# dc_q84_v1.net
KiCad netlist of a schematic drawn in EAGLE
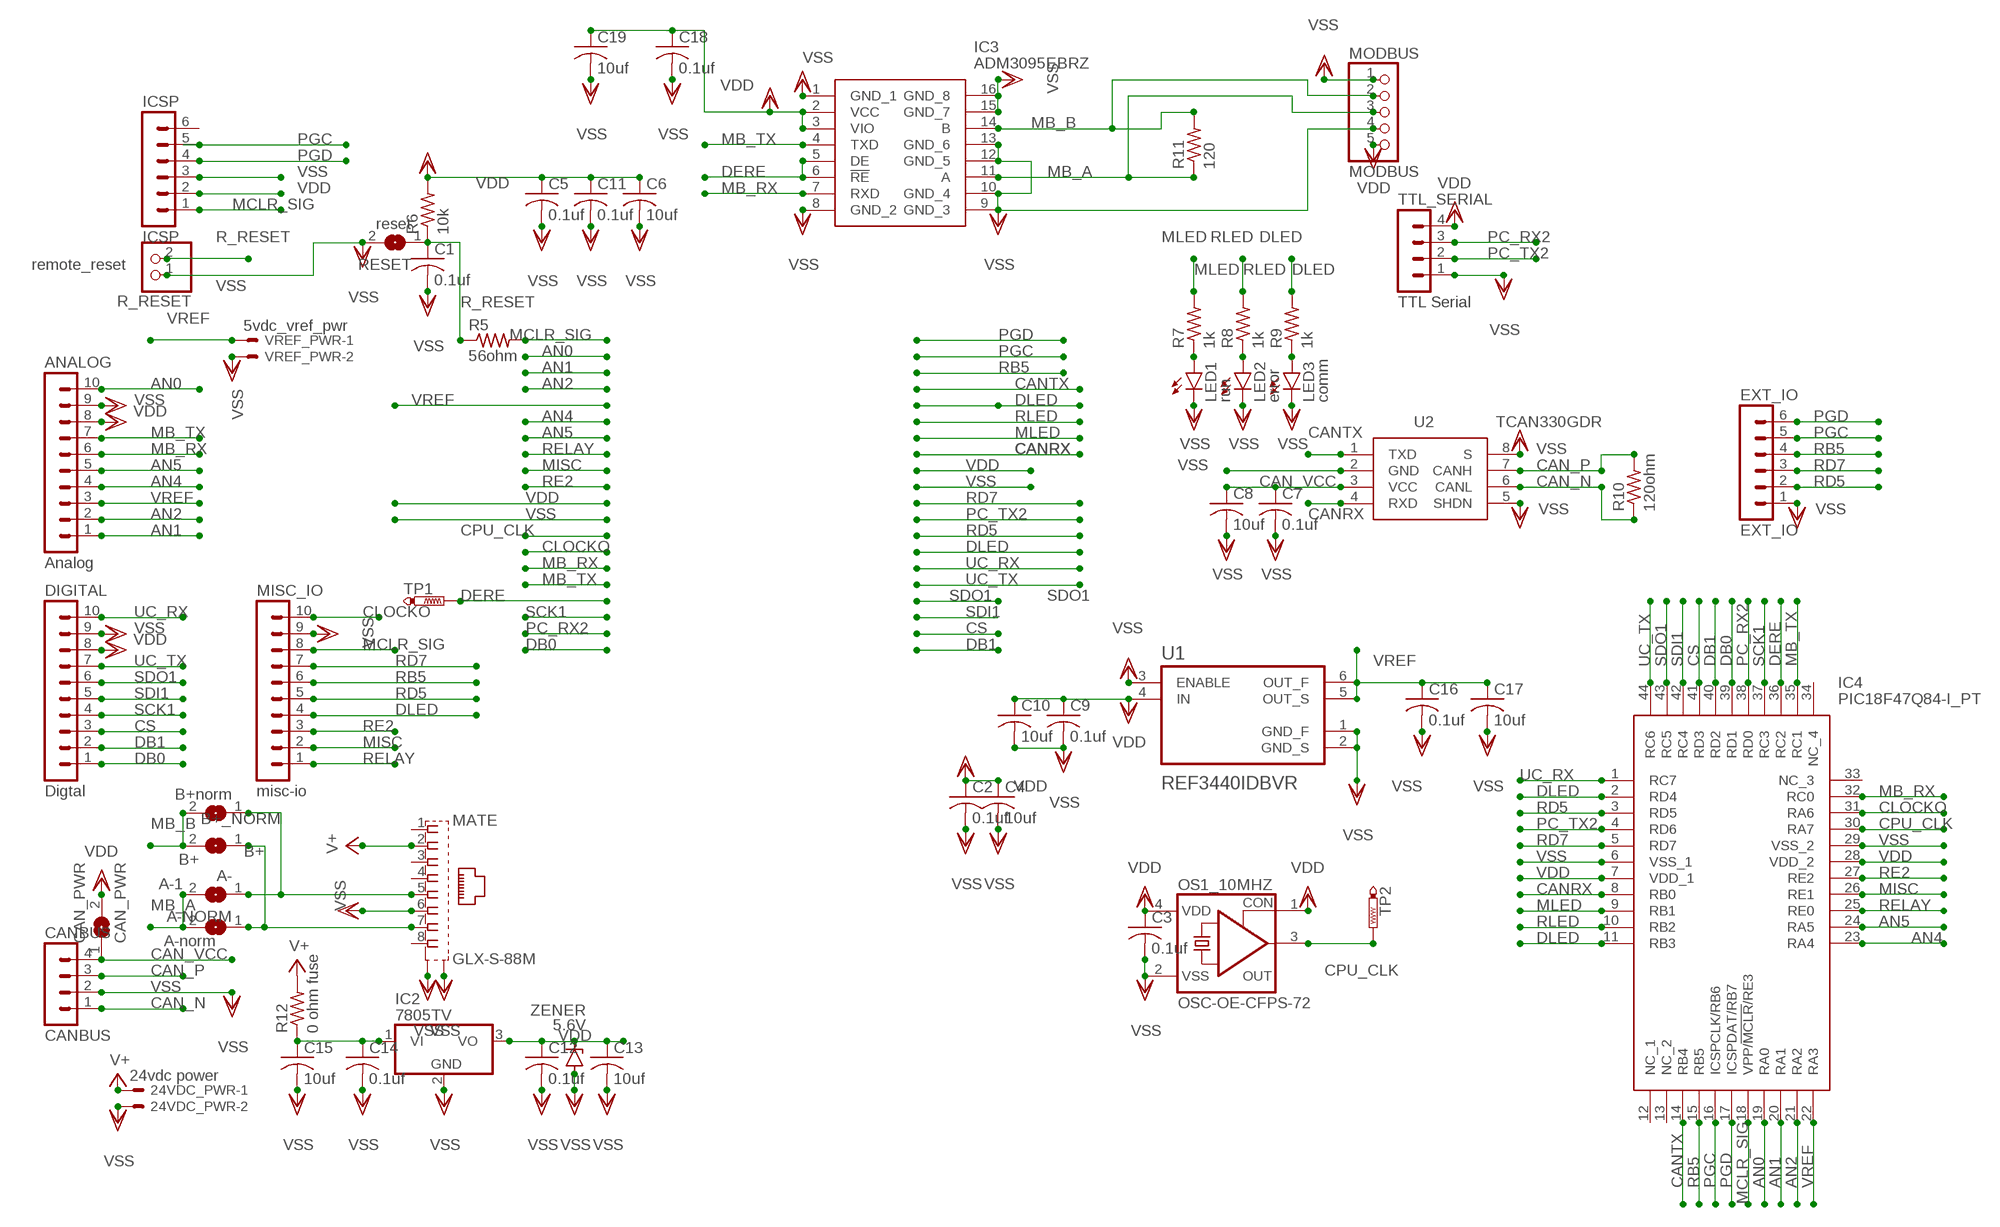
[diagram p0: schematic, sheet 1]

(export (version "E")
  (design (tool "Eeschema 10.0.6"))
  (components
    (comp (ref "24VDC_PWR")
      (value "24vdc power")
      (footprint "eagle-import:22-23-2021")
      (fields (field (name "MF") "MOLEX") (field (name "MPN") "22-23-2021"))
      (libsource (lib "eagle-import") (part "22-23-2021"))
    )
    (comp (ref "A-1") (value "A-") (footprint "eagle-import:SJ") (libsource (lib "eagle-import") (part "SJ")))
    (comp (ref "A-NORM")
      (value "A-norm")
      (footprint "eagle-import:SJ")
      (libsource (lib "eagle-import") (part "SJ"))
    )
    (comp (ref "ANALOG")
      (value "Analog")
      (footprint "eagle-import:MA10-1")
      (libsource (lib "eagle-import") (part "MA10-1"))
    )
    (comp (ref "B+") (value "B+") (footprint "eagle-import:SJ") (libsource (lib "eagle-import") (part "SJ")))
    (comp (ref "B+_NORM")
      (value "B+norm")
      (footprint "eagle-import:SJ")
      (libsource (lib "eagle-import") (part "SJ"))
    )
    (comp (ref "C1")
      (value "0.1uf")
      (footprint "eagle-import:C0805")
      (libsource (lib "eagle-import") (part "C-USC0805"))
    )
    (comp (ref "C2")
      (value "0.1uf")
      (footprint "eagle-import:C0805")
      (libsource (lib "eagle-import") (part "C-USC0805"))
    )
    (comp (ref "C3")
      (value "0.1uf")
      (footprint "eagle-import:C0805")
      (libsource (lib "eagle-import") (part "C-USC0805"))
    )
    (comp (ref "C4")
      (value "10uf")
      (footprint "eagle-import:C0805")
      (libsource (lib "eagle-import") (part "C-USC0805"))
    )
    (comp (ref "C5")
      (value "0.1uf")
      (footprint "eagle-import:C0805")
      (libsource (lib "eagle-import") (part "C-USC0805"))
    )
    (comp (ref "C6")
      (value "10uf")
      (footprint "eagle-import:C0805")
      (libsource (lib "eagle-import") (part "C-USC0805"))
    )
    (comp (ref "C7")
      (value "0.1uf")
      (footprint "eagle-import:C0805")
      (libsource (lib "eagle-import") (part "C-USC0805"))
    )
    (comp (ref "C8")
      (value "10uf")
      (footprint "eagle-import:C0805")
      (libsource (lib "eagle-import") (part "C-USC0805"))
    )
    (comp (ref "C9")
      (value "0.1uf")
      (footprint "eagle-import:C0805")
      (libsource (lib "eagle-import") (part "C-USC0805"))
    )
    (comp (ref "C10")
      (value "10uf")
      (footprint "eagle-import:C0805")
      (libsource (lib "eagle-import") (part "C-USC0805"))
    )
    (comp (ref "C11")
      (value "0.1uf")
      (footprint "eagle-import:C0805")
      (libsource (lib "eagle-import") (part "C-USC0805"))
    )
    (comp (ref "C12")
      (value "0.1uf")
      (footprint "eagle-import:C0805")
      (libsource (lib "eagle-import") (part "C-USC0805"))
    )
    (comp (ref "C13")
      (value "10uf")
      (footprint "eagle-import:C0805")
      (libsource (lib "eagle-import") (part "C-USC0805"))
    )
    (comp (ref "C14")
      (value "0.1uf")
      (footprint "eagle-import:C0805")
      (libsource (lib "eagle-import") (part "C-USC0805"))
    )
    (comp (ref "C15")
      (value "10uf")
      (footprint "eagle-import:C0805")
      (libsource (lib "eagle-import") (part "C-USC0805"))
    )
    (comp (ref "C16")
      (value "0.1uf")
      (footprint "eagle-import:C0805")
      (libsource (lib "eagle-import") (part "C-USC0805"))
    )
    (comp (ref "C17")
      (value "10uf")
      (footprint "eagle-import:C0805")
      (libsource (lib "eagle-import") (part "C-USC0805"))
    )
    (comp (ref "C18")
      (value "0.1uf")
      (footprint "eagle-import:C0805")
      (libsource (lib "eagle-import") (part "C-USC0805"))
    )
    (comp (ref "C19")
      (value "10uf")
      (footprint "eagle-import:C0805")
      (libsource (lib "eagle-import") (part "C-USC0805"))
    )
    (comp (ref "CANBUS")
      (value "CANBUS")
      (footprint "eagle-import:MA04-1")
      (libsource (lib "eagle-import") (part "MA04-1"))
    )
    (comp (ref "CAN_PWR")
      (value "CAN_PWR")
      (footprint "eagle-import:SJ")
      (libsource (lib "eagle-import") (part "SJ"))
    )
    (comp (ref "DIGITAL")
      (value "Digtal")
      (footprint "eagle-import:MA10-1")
      (libsource (lib "eagle-import") (part "MA10-1"))
    )
    (comp (ref "EXT_IO")
      (value "EXT_IO")
      (footprint "eagle-import:MA06-1")
      (libsource (lib "eagle-import") (part "MA06-1"))
    )
    (comp (ref "IC2")
      (value "7805TV")
      (footprint "eagle-import:TO220V")
      (libsource (lib "eagle-import") (part "78TV05"))
    )
    (comp (ref "IC3")
      (value "ADM3095EBRZ")
      (footprint "eagle-import:SOIC127P600X175-16N")
      (fields (field (name "MOUSER_PART_NUMBER") "584-ADM3095EBRZ"))
      (libsource (lib "eagle-import") (part "ADM3095EBRZ"))
    )
    (comp (ref "IC4")
      (value "PIC18F47Q84-I_PT")
      (footprint "eagle-import:QFP80P1200X1200X120-44N")
      (fields
        (field (name "MANUFACTURER_PART_NUMBER") "PIC18F47Q84-I/PT")
        (field (name "MOUSER_PART_NUMBER") "579-PIC18F47Q84-I/PT")
      )
      (libsource (lib "eagle-import") (part "PIC18F47Q84-I_PT"))
    )
    (comp (ref "ICSP")
      (value "ICSP")
      (footprint "eagle-import:MA06-1")
      (libsource (lib "eagle-import") (part "MA06-1"))
    )
    (comp (ref "LED1")
      (value "run")
      (footprint "eagle-import:CHIPLED_0805")
      (libsource (lib "eagle-import") (part "LEDCHIPLED_0805"))
    )
    (comp (ref "LED2")
      (value "error")
      (footprint "eagle-import:CHIPLED_0805")
      (libsource (lib "eagle-import") (part "LEDCHIPLED_0805"))
    )
    (comp (ref "LED3")
      (value "comm")
      (footprint "eagle-import:CHIPLED_0805")
      (libsource (lib "eagle-import") (part "LEDCHIPLED_0805"))
    )
    (comp (ref "MATE")
      (value "GLX-S-88M")
      (footprint "eagle-import:GLX-S-88M")
      (libsource (lib "eagle-import") (part "GLX-S-88M"))
    )
    (comp (ref "MISC_IO")
      (value "misc-io")
      (footprint "eagle-import:MA10-1")
      (libsource (lib "eagle-import") (part "MA10-1"))
    )
    (comp (ref "MODBUS")
      (value "MODBUS")
      (footprint "eagle-import:1X05")
      (libsource (lib "eagle-import") (part "PINHD-1X5"))
    )
    (comp (ref "OS1_10MHZ")
      (value "OSC-OE-CFPS-72")
      (footprint "eagle-import:7.2X5.2-4-PAD")
      (libsource (lib "eagle-import") (part "OSC-OE-CFPS-72"))
    )
    (comp (ref "R5")
      (value "56ohm")
      (footprint "eagle-import:R0805")
      (libsource (lib "eagle-import") (part "R-US_R0805"))
    )
    (comp (ref "R6")
      (value "10k")
      (footprint "eagle-import:R0805")
      (libsource (lib "eagle-import") (part "R-US_R0805"))
    )
    (comp (ref "R7")
      (value "1k")
      (footprint "eagle-import:R0805")
      (libsource (lib "eagle-import") (part "R-US_R0805"))
    )
    (comp (ref "R8")
      (value "1k")
      (footprint "eagle-import:R0805")
      (libsource (lib "eagle-import") (part "R-US_R0805"))
    )
    (comp (ref "R9")
      (value "1k")
      (footprint "eagle-import:R0805")
      (libsource (lib "eagle-import") (part "R-US_R0805"))
    )
    (comp (ref "R10")
      (value "120ohm")
      (footprint "eagle-import:R0805")
      (libsource (lib "eagle-import") (part "R-US_R0805"))
    )
    (comp (ref "R11")
      (value "120")
      (footprint "eagle-import:R0805")
      (libsource (lib "eagle-import") (part "R-US_R0805"))
    )
    (comp (ref "R12")
      (value "0 ohm fuse")
      (footprint "eagle-import:R1206")
      (libsource (lib "eagle-import") (part "R-US_R1206"))
    )
    (comp (ref "RESET")
      (value "reset")
      (footprint "eagle-import:SJ")
      (libsource (lib "eagle-import") (part "SJ"))
    )
    (comp (ref "R_RESET")
      (value "remote_reset")
      (footprint "eagle-import:1X02")
      (libsource (lib "eagle-import") (part "PINHD-1X2"))
    )
    (comp (ref "TP1")
      (value "PTR1PAD1-13")
      (footprint "eagle-import:P1-13")
      (libsource (lib "eagle-import") (part "PTR1PAD1-13"))
    )
    (comp (ref "TP2")
      (value "PTR1PAD1-13")
      (footprint "eagle-import:P1-13")
      (libsource (lib "eagle-import") (part "PTR1PAD1-13"))
    )
    (comp (ref "TTL_SERIAL")
      (value "TTL Serial")
      (footprint "eagle-import:MA04-1")
      (libsource (lib "eagle-import") (part "MA04-1"))
    )
    (comp (ref "U1")
      (value "REF3440IDBVR")
      (footprint "eagle-import:SOT95P280X145-6N")
      (fields (field (name "MF") "Texas Instruments"))
      (libsource (lib "eagle-import") (part "REF3440IDBVR"))
    )
    (comp (ref "U2")
      (value "TCAN330GDR")
      (footprint "eagle-import:SOIC127P600X175-8N")
      (fields (field (name "MOUSER_PART_NUMBER") "595-TCAN330GDR"))
      (libsource (lib "eagle-import") (part "TCAN330GDR"))
    )
    (comp (ref "VREF_PWR")
      (value "5vdc_vref_pwr")
      (footprint "eagle-import:22-23-2021")
      (fields (field (name "MF") "MOLEX") (field (name "MPN") "22-23-2021"))
      (libsource (lib "eagle-import") (part "22-23-2021"))
    )
    (comp (ref "ZENER")
      (value "5.6V")
      (footprint "eagle-import:SMB")
      (libsource (lib "eagle-import") (part "ZENER-DIODESMB"))
    )
  )
  (nets
    (net (code "1") (name "/AN0") (class "Default")
      (node (ref "ANALOG") (pin "10") (pinfunction "10_10") (pintype "passive"))
      (node (ref "IC4") (pin "19") (pinfunction "RA0_19") (pintype "bidirectional"))
    )
    (net (code "2") (name "/AN1") (class "Default")
      (node (ref "ANALOG") (pin "1") (pinfunction "1_1") (pintype "passive"))
      (node (ref "IC4") (pin "20") (pinfunction "RA1_20") (pintype "bidirectional"))
    )
    (net (code "3") (name "/AN2") (class "Default")
      (node (ref "ANALOG") (pin "2") (pinfunction "2_2") (pintype "passive"))
      (node (ref "IC4") (pin "21") (pinfunction "RA2_21") (pintype "bidirectional"))
    )
    (net (code "4") (name "/AN4") (class "Default")
      (node (ref "ANALOG") (pin "4") (pinfunction "4_4") (pintype "passive"))
      (node (ref "IC4") (pin "23") (pinfunction "RA4_23") (pintype "bidirectional"))
    )
    (net (code "5") (name "/AN5") (class "Default")
      (node (ref "ANALOG") (pin "5") (pinfunction "5_5") (pintype "passive"))
      (node (ref "IC4") (pin "24") (pinfunction "RA5_24") (pintype "bidirectional"))
    )
    (net (code "6") (name "/CANRX") (class "Default")
      (node (ref "IC4") (pin "8") (pinfunction "RB0_8") (pintype "bidirectional"))
      (node (ref "U2") (pin "4") (pinfunction "RXD_4") (pintype "output"))
    )
    (net (code "7") (name "/CANTX") (class "Default")
      (node (ref "IC4") (pin "14") (pinfunction "RB4_14") (pintype "bidirectional"))
      (node (ref "U2") (pin "1") (pinfunction "TXD_1") (pintype "input"))
    )
    (net (code "8") (name "/CAN_N") (class "Default")
      (node (ref "CANBUS") (pin "1") (pinfunction "1_1") (pintype "passive"))
      (node (ref "R10") (pin "1") (pinfunction "1_1") (pintype "passive"))
      (node (ref "U2") (pin "6") (pinfunction "CANL_6") (pintype "bidirectional"))
    )
    (net (code "9") (name "/CAN_P") (class "Default")
      (node (ref "CANBUS") (pin "3") (pinfunction "3_3") (pintype "passive"))
      (node (ref "R10") (pin "2") (pinfunction "2_2") (pintype "passive"))
      (node (ref "U2") (pin "7") (pinfunction "CANH_7") (pintype "bidirectional"))
    )
    (net (code "10") (name "/CAN_VCC") (class "Default")
      (node (ref "C7") (pin "1") (pinfunction "1_1") (pintype "passive"))
      (node (ref "C8") (pin "1") (pinfunction "1_1") (pintype "passive"))
      (node (ref "CANBUS") (pin "4") (pinfunction "4_4") (pintype "passive"))
      (node (ref "CAN_PWR") (pin "1") (pinfunction "1_1") (pintype "passive"))
      (node (ref "U2") (pin "3") (pinfunction "VCC_3") (pintype "power_in"))
    )
    (net (code "11") (name "/CLOCKO") (class "Default")
      (node (ref "IC4") (pin "31") (pinfunction "RA6_31") (pintype "bidirectional"))
      (node (ref "MISC_IO") (pin "10") (pinfunction "10_10") (pintype "passive"))
    )
    (net (code "12") (name "/CPU_CLK") (class "Default")
      (node (ref "IC4") (pin "30") (pinfunction "RA7_30") (pintype "bidirectional"))
      (node (ref "OS1_10MHZ") (pin "3") (pinfunction "OUT_3") (pintype "output"))
      (node (ref "TP2") (pin "TP") (pinfunction "TP_TP") (pintype "input"))
    )
    (net (code "13") (name "/CS") (class "Default")
      (node (ref "DIGITAL") (pin "3") (pinfunction "3_3") (pintype "passive"))
      (node (ref "IC4") (pin "41") (pinfunction "RD3_41") (pintype "bidirectional"))
    )
    (net (code "14") (name "/DB0") (class "Default")
      (node (ref "DIGITAL") (pin "1") (pinfunction "1_1") (pintype "passive"))
      (node (ref "IC4") (pin "39") (pinfunction "RD1_39") (pintype "bidirectional"))
    )
    (net (code "15") (name "/DB1") (class "Default")
      (node (ref "DIGITAL") (pin "2") (pinfunction "2_2") (pintype "passive"))
      (node (ref "IC4") (pin "40") (pinfunction "RD2_40") (pintype "bidirectional"))
    )
    (net (code "16") (name "/DERE") (class "Default")
      (node (ref "IC3") (pin "5") (pinfunction "DE_5") (pintype "input"))
      (node (ref "IC3") (pin "6") (pinfunction "~{RE}_6") (pintype "input"))
      (node (ref "IC4") (pin "36") (pinfunction "RC2_36") (pintype "bidirectional"))
      (node (ref "TP1") (pin "TP") (pinfunction "TP_TP") (pintype "input"))
    )
    (net (code "17") (name "/DLED") (class "Default")
      (node (ref "IC4") (pin "11") (pinfunction "RB3_11") (pintype "bidirectional"))
      (node (ref "IC4") (pin "2") (pinfunction "RD4_2") (pintype "bidirectional"))
      (node (ref "MISC_IO") (pin "4") (pinfunction "4_4") (pintype "passive"))
      (node (ref "R9") (pin "2") (pinfunction "2_2") (pintype "passive"))
    )
    (net (code "18") (name "/MB_A") (class "Default")
      (node (ref "A-1") (pin "2") (pinfunction "2_2") (pintype "passive"))
      (node (ref "A-NORM") (pin "2") (pinfunction "2_2") (pintype "passive"))
      (node (ref "IC3") (pin "11") (pinfunction "A_11") (pintype "bidirectional"))
      (node (ref "MODBUS") (pin "3") (pinfunction "3_3") (pintype "passive"))
      (node (ref "R11") (pin "1") (pinfunction "1_1") (pintype "passive"))
    )
    (net (code "19") (name "/MB_B") (class "Default")
      (node (ref "B+") (pin "2") (pinfunction "2_2") (pintype "passive"))
      (node (ref "B+_NORM") (pin "2") (pinfunction "2_2") (pintype "passive"))
      (node (ref "IC3") (pin "14") (pinfunction "B_14") (pintype "bidirectional"))
      (node (ref "MODBUS") (pin "2") (pinfunction "2_2") (pintype "passive"))
      (node (ref "R11") (pin "2") (pinfunction "2_2") (pintype "passive"))
    )
    (net (code "20") (name "/MB_RX") (class "Default")
      (node (ref "ANALOG") (pin "6") (pinfunction "6_6") (pintype "passive"))
      (node (ref "IC3") (pin "7") (pinfunction "RXD_7") (pintype "output"))
      (node (ref "IC4") (pin "32") (pinfunction "RC0_32") (pintype "bidirectional"))
    )
    (net (code "21") (name "/MB_TX") (class "Default")
      (node (ref "ANALOG") (pin "7") (pinfunction "7_7") (pintype "passive"))
      (node (ref "IC3") (pin "4") (pinfunction "TXD_4") (pintype "input"))
      (node (ref "IC4") (pin "35") (pinfunction "RC1_35") (pintype "bidirectional"))
    )
    (net (code "22") (name "/MCLR_SIG") (class "Default")
      (node (ref "IC4") (pin "18") (pinfunction "VPP/~{MCLR}/RE3_18") (pintype "bidirectional"))
      (node (ref "ICSP") (pin "1") (pinfunction "1_1") (pintype "passive"))
      (node (ref "MISC_IO") (pin "8") (pinfunction "8_8") (pintype "passive"))
      (node (ref "R5") (pin "2") (pinfunction "2_2") (pintype "passive"))
    )
    (net (code "23") (name "/MISC") (class "Default")
      (node (ref "IC4") (pin "26") (pinfunction "RE1_26") (pintype "bidirectional"))
      (node (ref "MISC_IO") (pin "2") (pinfunction "2_2") (pintype "passive"))
    )
    (net (code "24") (name "/MLED") (class "Default")
      (node (ref "IC4") (pin "9") (pinfunction "RB1_9") (pintype "bidirectional"))
      (node (ref "R7") (pin "2") (pinfunction "2_2") (pintype "passive"))
    )
    (net (code "25") (name "/PC_RX2") (class "Default")
      (node (ref "IC4") (pin "38") (pinfunction "RD0_38") (pintype "bidirectional"))
      (node (ref "TTL_SERIAL") (pin "3") (pinfunction "3_3") (pintype "passive"))
    )
    (net (code "26") (name "/PC_TX2") (class "Default")
      (node (ref "IC4") (pin "4") (pinfunction "RD6_4") (pintype "bidirectional"))
      (node (ref "TTL_SERIAL") (pin "2") (pinfunction "2_2") (pintype "passive"))
    )
    (net (code "27") (name "/PGC") (class "Default")
      (node (ref "EXT_IO") (pin "5") (pinfunction "5_5") (pintype "passive"))
      (node (ref "IC4") (pin "16") (pinfunction "ICSPCLK/RB6_16") (pintype "bidirectional"))
      (node (ref "ICSP") (pin "5") (pinfunction "5_5") (pintype "passive"))
    )
    (net (code "28") (name "/PGD") (class "Default")
      (node (ref "EXT_IO") (pin "6") (pinfunction "6_6") (pintype "passive"))
      (node (ref "IC4") (pin "17") (pinfunction "ICSPDAT/RB7_17") (pintype "bidirectional"))
      (node (ref "ICSP") (pin "4") (pinfunction "4_4") (pintype "passive"))
    )
    (net (code "29") (name "/RB5") (class "Default")
      (node (ref "EXT_IO") (pin "4") (pinfunction "4_4") (pintype "passive"))
      (node (ref "IC4") (pin "15") (pinfunction "RB5_15") (pintype "bidirectional"))
      (node (ref "MISC_IO") (pin "6") (pinfunction "6_6") (pintype "passive"))
    )
    (net (code "30") (name "/RD5") (class "Default")
      (node (ref "EXT_IO") (pin "2") (pinfunction "2_2") (pintype "passive"))
      (node (ref "IC4") (pin "3") (pinfunction "RD5_3") (pintype "bidirectional"))
      (node (ref "MISC_IO") (pin "5") (pinfunction "5_5") (pintype "passive"))
    )
    (net (code "31") (name "/RD7") (class "Default")
      (node (ref "EXT_IO") (pin "3") (pinfunction "3_3") (pintype "passive"))
      (node (ref "IC4") (pin "5") (pinfunction "RD7_5") (pintype "bidirectional"))
      (node (ref "MISC_IO") (pin "7") (pinfunction "7_7") (pintype "passive"))
    )
    (net (code "32") (name "/RE2") (class "Default")
      (node (ref "IC4") (pin "27") (pinfunction "RE2_27") (pintype "bidirectional"))
      (node (ref "MISC_IO") (pin "3") (pinfunction "3_3") (pintype "passive"))
    )
    (net (code "33") (name "/RELAY") (class "Default")
      (node (ref "IC4") (pin "25") (pinfunction "RE0_25") (pintype "bidirectional"))
      (node (ref "MISC_IO") (pin "1") (pinfunction "1_1") (pintype "passive"))
    )
    (net (code "34") (name "/RLED") (class "Default")
      (node (ref "IC4") (pin "10") (pinfunction "RB2_10") (pintype "bidirectional"))
      (node (ref "R8") (pin "2") (pinfunction "2_2") (pintype "passive"))
    )
    (net (code "35") (name "/R_RESET") (class "Default")
      (node (ref "C1") (pin "1") (pinfunction "1_1") (pintype "passive"))
      (node (ref "R5") (pin "1") (pinfunction "1_1") (pintype "passive"))
      (node (ref "R6") (pin "1") (pinfunction "1_1") (pintype "passive"))
      (node (ref "RESET") (pin "1") (pinfunction "1_1") (pintype "passive"))
      (node (ref "R_RESET") (pin "2") (pinfunction "2_2") (pintype "passive"))
    )
    (net (code "36") (name "/SCK1") (class "Default")
      (node (ref "DIGITAL") (pin "4") (pinfunction "4_4") (pintype "passive"))
      (node (ref "IC4") (pin "37") (pinfunction "RC3_37") (pintype "bidirectional"))
    )
    (net (code "37") (name "/SDI1") (class "Default")
      (node (ref "DIGITAL") (pin "5") (pinfunction "5_5") (pintype "passive"))
      (node (ref "IC4") (pin "42") (pinfunction "RC4_42") (pintype "bidirectional"))
    )
    (net (code "38") (name "/SDO1") (class "Default")
      (node (ref "DIGITAL") (pin "6") (pinfunction "6_6") (pintype "passive"))
      (node (ref "IC4") (pin "43") (pinfunction "RC5_43") (pintype "bidirectional"))
    )
    (net (code "39") (name "/UC_RX") (class "Default")
      (node (ref "DIGITAL") (pin "10") (pinfunction "10_10") (pintype "passive"))
      (node (ref "IC4") (pin "1") (pinfunction "RC7_1") (pintype "bidirectional"))
    )
    (net (code "40") (name "/UC_TX") (class "Default")
      (node (ref "DIGITAL") (pin "7") (pinfunction "7_7") (pintype "passive"))
      (node (ref "IC4") (pin "44") (pinfunction "RC6_44") (pintype "bidirectional"))
    )
    (net (code "41") (name "/VREF") (class "Default")
      (node (ref "ANALOG") (pin "3") (pinfunction "3_3") (pintype "passive"))
      (node (ref "C16") (pin "1") (pinfunction "1_1") (pintype "passive"))
      (node (ref "C17") (pin "1") (pinfunction "1_1") (pintype "passive"))
      (node (ref "IC4") (pin "22") (pinfunction "RA3_22") (pintype "bidirectional"))
      (node (ref "U1") (pin "5") (pinfunction "OUT_S_5") (pintype "output"))
      (node (ref "U1") (pin "6") (pinfunction "OUT_F_6") (pintype "output"))
      (node (ref "VREF_PWR") (pin "1") (pinfunction "S_1") (pintype "passive"))
    )
    (net (code "42") (name "Net-(A-1-Pad1)") (class "Default")
      (node (ref "A-1") (pin "1") (pinfunction "1_1") (pintype "passive"))
      (node (ref "B+_NORM") (pin "1") (pinfunction "1_1") (pintype "passive"))
      (node (ref "MATE") (pin "5") (pinfunction "5_5") (pintype "passive"))
    )
    (net (code "43") (name "Net-(A-NORM-Pad1)") (class "Default")
      (node (ref "A-NORM") (pin "1") (pinfunction "1_1") (pintype "passive"))
      (node (ref "B+") (pin "1") (pinfunction "1_1") (pintype "passive"))
      (node (ref "MATE") (pin "7") (pinfunction "7_7") (pintype "passive"))
    )
    (net (code "44") (name "Net-(IC2-VI)") (class "Default")
      (node (ref "C14") (pin "1") (pinfunction "1_1") (pintype "passive"))
      (node (ref "C15") (pin "1") (pinfunction "1_1") (pintype "passive"))
      (node (ref "IC2") (pin "1") (pinfunction "VI_1") (pintype "input"))
      (node (ref "R12") (pin "1") (pinfunction "1_1") (pintype "passive"))
    )
    (net (code "45") (name "Net-(LED1-PadA)") (class "Default")
      (node (ref "LED1") (pin "A") (pinfunction "A_A") (pintype "passive"))
      (node (ref "R7") (pin "1") (pinfunction "1_1") (pintype "passive"))
    )
    (net (code "46") (name "Net-(LED2-PadA)") (class "Default")
      (node (ref "LED2") (pin "A") (pinfunction "A_A") (pintype "passive"))
      (node (ref "R8") (pin "1") (pinfunction "1_1") (pintype "passive"))
    )
    (net (code "47") (name "Net-(LED3-PadA)") (class "Default")
      (node (ref "LED3") (pin "A") (pinfunction "A_A") (pintype "passive"))
      (node (ref "R9") (pin "1") (pinfunction "1_1") (pintype "passive"))
    )
    (net (code "48") (name "V+") (class "Default")
      (node (ref "24VDC_PWR") (pin "1") (pinfunction "S_1") (pintype "passive"))
      (node (ref "MATE") (pin "2") (pinfunction "2_2") (pintype "passive"))
      (node (ref "R12") (pin "2") (pinfunction "2_2") (pintype "passive"))
    )
    (net (code "49") (name "VDD") (class "Default")
      (node (ref "ANALOG") (pin "8") (pinfunction "8_8") (pintype "passive"))
      (node (ref "C10") (pin "1") (pinfunction "1_1") (pintype "passive"))
      (node (ref "C11") (pin "1") (pinfunction "1_1") (pintype "passive"))
      (node (ref "C12") (pin "1") (pinfunction "1_1") (pintype "passive"))
      (node (ref "C13") (pin "1") (pinfunction "1_1") (pintype "passive"))
      (node (ref "C18") (pin "1") (pinfunction "1_1") (pintype "passive"))
      (node (ref "C19") (pin "1") (pinfunction "1_1") (pintype "passive"))
      (node (ref "C2") (pin "1") (pinfunction "1_1") (pintype "passive"))
      (node (ref "C3") (pin "1") (pinfunction "1_1") (pintype "passive"))
      (node (ref "C4") (pin "1") (pinfunction "1_1") (pintype "passive"))
      (node (ref "C5") (pin "1") (pinfunction "1_1") (pintype "passive"))
      (node (ref "C6") (pin "1") (pinfunction "1_1") (pintype "passive"))
      (node (ref "C9") (pin "1") (pinfunction "1_1") (pintype "passive"))
      (node (ref "CAN_PWR") (pin "2") (pinfunction "2_2") (pintype "passive"))
      (node (ref "DIGITAL") (pin "8") (pinfunction "8_8") (pintype "passive"))
      (node (ref "IC2") (pin "3") (pinfunction "VO_3") (pintype "passive"))
      (node (ref "IC3") (pin "2") (pinfunction "VCC_2") (pintype "power_in"))
      (node (ref "IC3") (pin "3") (pinfunction "VIO_3") (pintype "power_in"))
      (node (ref "IC4") (pin "28") (pinfunction "VDD_2_28") (pintype "bidirectional"))
      (node (ref "IC4") (pin "7") (pinfunction "VDD_1_7") (pintype "bidirectional"))
      (node (ref "ICSP") (pin "2") (pinfunction "2_2") (pintype "passive"))
      (node (ref "MODBUS") (pin "5") (pinfunction "5_5") (pintype "passive"))
      (node (ref "OS1_10MHZ") (pin "1") (pinfunction "CON_1") (pintype "input"))
      (node (ref "OS1_10MHZ") (pin "4") (pinfunction "VDD_4") (pintype "power_in"))
      (node (ref "R6") (pin "2") (pinfunction "2_2") (pintype "passive"))
      (node (ref "TTL_SERIAL") (pin "4") (pinfunction "4_4") (pintype "passive"))
      (node (ref "U1") (pin "4") (pinfunction "IN_4") (pintype "input"))
      (node (ref "ZENER") (pin "C") (pinfunction "C_C") (pintype "passive"))
    )
    (net (code "50") (name "VSS") (class "Default")
      (node (ref "24VDC_PWR") (pin "2") (pinfunction "S_2") (pintype "passive"))
      (node (ref "ANALOG") (pin "9") (pinfunction "9_9") (pintype "passive"))
      (node (ref "C1") (pin "2") (pinfunction "2_2") (pintype "passive"))
      (node (ref "C10") (pin "2") (pinfunction "2_2") (pintype "passive"))
      (node (ref "C11") (pin "2") (pinfunction "2_2") (pintype "passive"))
      (node (ref "C12") (pin "2") (pinfunction "2_2") (pintype "passive"))
      (node (ref "C13") (pin "2") (pinfunction "2_2") (pintype "passive"))
      (node (ref "C14") (pin "2") (pinfunction "2_2") (pintype "passive"))
      (node (ref "C15") (pin "2") (pinfunction "2_2") (pintype "passive"))
      (node (ref "C16") (pin "2") (pinfunction "2_2") (pintype "passive"))
      (node (ref "C17") (pin "2") (pinfunction "2_2") (pintype "passive"))
      (node (ref "C18") (pin "2") (pinfunction "2_2") (pintype "passive"))
      (node (ref "C19") (pin "2") (pinfunction "2_2") (pintype "passive"))
      (node (ref "C2") (pin "2") (pinfunction "2_2") (pintype "passive"))
      (node (ref "C3") (pin "2") (pinfunction "2_2") (pintype "passive"))
      (node (ref "C4") (pin "2") (pinfunction "2_2") (pintype "passive"))
      (node (ref "C5") (pin "2") (pinfunction "2_2") (pintype "passive"))
      (node (ref "C6") (pin "2") (pinfunction "2_2") (pintype "passive"))
      (node (ref "C7") (pin "2") (pinfunction "2_2") (pintype "passive"))
      (node (ref "C8") (pin "2") (pinfunction "2_2") (pintype "passive"))
      (node (ref "C9") (pin "2") (pinfunction "2_2") (pintype "passive"))
      (node (ref "CANBUS") (pin "2") (pinfunction "2_2") (pintype "passive"))
      (node (ref "DIGITAL") (pin "9") (pinfunction "9_9") (pintype "passive"))
      (node (ref "EXT_IO") (pin "1") (pinfunction "1_1") (pintype "passive"))
      (node (ref "IC2") (pin "2") (pinfunction "GND_2") (pintype "passive"))
      (node (ref "IC3") (pin "1") (pinfunction "GND_1_1") (pintype "power_in"))
      (node (ref "IC3") (pin "10") (pinfunction "GND_4_10") (pintype "power_in"))
      (node (ref "IC3") (pin "12") (pinfunction "GND_5_12") (pintype "power_in"))
      (node (ref "IC3") (pin "13") (pinfunction "GND_6_13") (pintype "power_in"))
      (node (ref "IC3") (pin "15") (pinfunction "GND_7_15") (pintype "power_in"))
      (node (ref "IC3") (pin "16") (pinfunction "GND_8_16") (pintype "power_in"))
      (node (ref "IC3") (pin "8") (pinfunction "GND_2_8") (pintype "power_in"))
      (node (ref "IC3") (pin "9") (pinfunction "GND_3_9") (pintype "power_in"))
      (node (ref "IC4") (pin "29") (pinfunction "VSS_2_29") (pintype "bidirectional"))
      (node (ref "IC4") (pin "6") (pinfunction "VSS_1_6") (pintype "bidirectional"))
      (node (ref "ICSP") (pin "3") (pinfunction "3_3") (pintype "passive"))
      (node (ref "LED1") (pin "C") (pinfunction "C_C") (pintype "passive"))
      (node (ref "LED2") (pin "C") (pinfunction "C_C") (pintype "passive"))
      (node (ref "LED3") (pin "C") (pinfunction "C_C") (pintype "passive"))
      (node (ref "MATE") (pin "6") (pinfunction "6_6") (pintype "passive"))
      (node (ref "MATE") (pin "S1") (pinfunction "S1_S1") (pintype "passive"))
      (node (ref "MATE") (pin "S2") (pinfunction "S2_S2") (pintype "passive"))
      (node (ref "MISC_IO") (pin "9") (pinfunction "9_9") (pintype "passive"))
      (node (ref "MODBUS") (pin "1") (pinfunction "1_1") (pintype "passive"))
      (node (ref "MODBUS") (pin "4") (pinfunction "4_4") (pintype "passive"))
      (node (ref "OS1_10MHZ") (pin "2") (pinfunction "VSS_2") (pintype "power_in"))
      (node (ref "RESET") (pin "2") (pinfunction "2_2") (pintype "passive"))
      (node (ref "R_RESET") (pin "1") (pinfunction "1_1") (pintype "passive"))
      (node (ref "TTL_SERIAL") (pin "1") (pinfunction "1_1") (pintype "passive"))
      (node (ref "U1") (pin "1") (pinfunction "GND_F_1") (pintype "power_in"))
      (node (ref "U1") (pin "2") (pinfunction "GND_S_2") (pintype "power_in"))
      (node (ref "U1") (pin "3") (pinfunction "ENABLE_3") (pintype "input"))
      (node (ref "U2") (pin "2") (pinfunction "GND_2") (pintype "power_in"))
      (node (ref "U2") (pin "5") (pinfunction "SHDN_5") (pintype "bidirectional"))
      (node (ref "U2") (pin "8") (pinfunction "S_8") (pintype "bidirectional"))
      (node (ref "VREF_PWR") (pin "2") (pinfunction "S_2") (pintype "passive"))
      (node (ref "ZENER") (pin "A") (pinfunction "A_A") (pintype "passive"))
    )
    (net (code "51") (name "unconnected-(IC4-NC_1-Pad12)") (class "Default")
      (node (ref "IC4") (pin "12") (pinfunction "NC_1_12") (pintype "bidirectional"))
    )
    (net (code "52") (name "unconnected-(IC4-NC_2-Pad13)") (class "Default")
      (node (ref "IC4") (pin "13") (pinfunction "NC_2_13") (pintype "bidirectional"))
    )
    (net (code "53") (name "unconnected-(IC4-NC_3-Pad33)") (class "Default")
      (node (ref "IC4") (pin "33") (pinfunction "NC_3_33") (pintype "bidirectional"))
    )
    (net (code "54") (name "unconnected-(IC4-NC_4-Pad34)") (class "Default")
      (node (ref "IC4") (pin "34") (pinfunction "NC_4_34") (pintype "bidirectional"))
    )
    (net (code "55") (name "unconnected-(ICSP-Pad6)") (class "Default")
      (node (ref "ICSP") (pin "6") (pinfunction "6_6") (pintype "passive"))
    )
    (net (code "56") (name "unconnected-(MATE-Pad1)") (class "Default")
      (node (ref "MATE") (pin "1") (pinfunction "1_1") (pintype "passive"))
    )
    (net (code "57") (name "unconnected-(MATE-Pad3)") (class "Default")
      (node (ref "MATE") (pin "3") (pinfunction "3_3") (pintype "passive"))
    )
    (net (code "58") (name "unconnected-(MATE-Pad4)") (class "Default")
      (node (ref "MATE") (pin "4") (pinfunction "4_4") (pintype "passive"))
    )
    (net (code "59") (name "unconnected-(MATE-Pad8)") (class "Default")
      (node (ref "MATE") (pin "8") (pinfunction "8_8") (pintype "passive"))
    )
  )
)
